# hellobusbridge_button.net
KiCad netlist of a schematic drawn in EAGLE
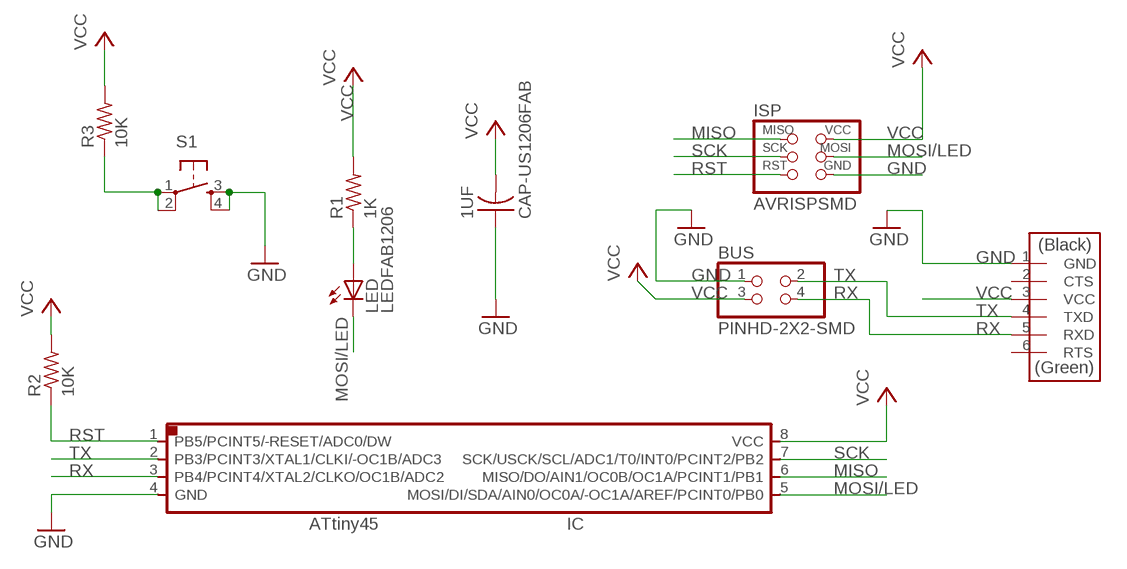
[diagram p0: schematic, sheet 1]

(export (version "E")
  (design (tool "Eeschema 10.0.6"))
  (components
    (comp (ref "1UF")
      (value "CAP-US1206FAB")
      (footprint "eagle-import:C1206FAB")
      (libsource (lib "eagle-import") (part "CAP-US1206FAB"))
    )
    (comp (ref "BUS")
      (value "PINHD-2X2-SMD")
      (footprint "eagle-import:2X02SMD")
      (libsource (lib "eagle-import") (part "PINHD-2X2-SMD"))
    )
    (comp (ref "IC")
      (value "IC")
      (footprint "eagle-import:SOIC8")
      (libsource (lib "eagle-import") (part "ATTINY45SI"))
    )
    (comp (ref "ISP")
      (value "AVRISPSMD")
      (footprint "eagle-import:2X03SMD")
      (libsource (lib "eagle-import") (part "AVRISPSMD"))
    )
    (comp (ref "LED")
      (value "LEDFAB1206")
      (footprint "eagle-import:LED1206FAB")
      (libsource (lib "eagle-import") (part "LEDFAB1206"))
    )
    (comp (ref "R1")
      (value "1K")
      (footprint "eagle-import:R1206FAB")
      (libsource (lib "eagle-import") (part "RES-US1206FAB"))
    )
    (comp (ref "R2")
      (value "10K")
      (footprint "eagle-import:R1206FAB")
      (libsource (lib "eagle-import") (part "RES-US1206FAB"))
    )
    (comp (ref "R3")
      (value "10K")
      (footprint "eagle-import:R1206FAB")
      (libsource (lib "eagle-import") (part "RES-US1206FAB"))
    )
    (comp (ref "S1")
      (value "6MM_SWITCH6MM_SWITCH")
      (footprint "eagle-import:6MM_SWITCH")
      (libsource (lib "eagle-import") (part "6MM_SWITCH6MM_SWITCH"))
    )
    (comp (ref "U$5")
      (value "FTDI-SMD-HEADER")
      (footprint "eagle-import:1X06SMD")
      (libsource (lib "eagle-import") (part "FTDI-SMD-HEADER"))
    )
  )
  (nets
    (net (code "1") (name "/MISO") (class "Default")
      (node (ref "IC") (pin "6") (pinfunction "MISO/DO/AIN1/OC0B/OC1A/PCINT1/PB1_6") (pintype "bidirectional"))
      (node (ref "ISP") (pin "1") (pinfunction "MISO_1") (pintype "passive"))
      (node (ref "R3") (pin "1") (pinfunction "1_1") (pintype "passive"))
      (node (ref "S1") (pin "1") (pinfunction "P_1") (pintype "passive"))
      (node (ref "S1") (pin "2") (pinfunction "P1_2") (pintype "passive"))
    )
    (net (code "2") (name "/MOSI{slash}LED") (class "Default")
      (node (ref "IC") (pin "5") (pinfunction "MOSI/DI/SDA/AIN0/OC0A/-OC1A/AREF/PCINT0/PB0_5") (pintype "bidirectional"))
      (node (ref "ISP") (pin "4") (pinfunction "MOSI_4") (pintype "passive"))
      (node (ref "LED") (pin "2") (pinfunction "C_2") (pintype "passive"))
    )
    (net (code "3") (name "/RST") (class "Default")
      (node (ref "IC") (pin "1") (pinfunction "PB5/PCINT5/-RESET/ADC0/DW_1") (pintype "bidirectional"))
      (node (ref "ISP") (pin "5") (pinfunction "RST_5") (pintype "passive"))
      (node (ref "R2") (pin "1") (pinfunction "1_1") (pintype "passive"))
    )
    (net (code "4") (name "/RX") (class "Default")
      (node (ref "BUS") (pin "4") (pinfunction "4_4") (pintype "passive"))
      (node (ref "IC") (pin "3") (pinfunction "PB4/PCINT4/XTAL2/CLKO/OC1B/ADC2_3") (pintype "bidirectional"))
      (node (ref "U$5") (pin "5") (pinfunction "RXD_5") (pintype "bidirectional"))
    )
    (net (code "5") (name "/SCK") (class "Default")
      (node (ref "IC") (pin "7") (pinfunction "SCK/USCK/SCL/ADC1/T0/INT0/PCINT2/PB2_7") (pintype "bidirectional"))
      (node (ref "ISP") (pin "3") (pinfunction "SCK_3") (pintype "passive"))
    )
    (net (code "6") (name "/TX") (class "Default")
      (node (ref "BUS") (pin "2") (pinfunction "2_2") (pintype "passive"))
      (node (ref "IC") (pin "2") (pinfunction "PB3/PCINT3/XTAL1/CLKI/-OC1B/ADC3_2") (pintype "bidirectional"))
      (node (ref "U$5") (pin "4") (pinfunction "TXD_4") (pintype "bidirectional"))
    )
    (net (code "7") (name "GND") (class "Default")
      (node (ref "1UF") (pin "1") (pinfunction "1_1") (pintype "passive"))
      (node (ref "BUS") (pin "1") (pinfunction "1_1") (pintype "passive"))
      (node (ref "IC") (pin "4") (pinfunction "GND_4") (pintype "bidirectional"))
      (node (ref "ISP") (pin "6") (pinfunction "GND_6") (pintype "passive"))
      (node (ref "S1") (pin "3") (pinfunction "S_3") (pintype "passive"))
      (node (ref "S1") (pin "4") (pinfunction "S1_4") (pintype "passive"))
      (node (ref "U$5") (pin "1") (pinfunction "GND_1") (pintype "bidirectional"))
    )
    (net (code "8") (name "Net-(LED-A)") (class "Default")
      (node (ref "LED") (pin "1") (pinfunction "A_1") (pintype "passive"))
      (node (ref "R1") (pin "1") (pinfunction "1_1") (pintype "passive"))
    )
    (net (code "9") (name "VCC") (class "Default")
      (node (ref "1UF") (pin "2") (pinfunction "2_2") (pintype "passive"))
      (node (ref "BUS") (pin "3") (pinfunction "3_3") (pintype "passive"))
      (node (ref "IC") (pin "8") (pinfunction "VCC_8") (pintype "bidirectional"))
      (node (ref "ISP") (pin "2") (pinfunction "VCC_2") (pintype "passive"))
      (node (ref "R1") (pin "2") (pinfunction "2_2") (pintype "passive"))
      (node (ref "R2") (pin "2") (pinfunction "2_2") (pintype "passive"))
      (node (ref "R3") (pin "2") (pinfunction "2_2") (pintype "passive"))
      (node (ref "U$5") (pin "3") (pinfunction "VCC_3") (pintype "bidirectional"))
    )
    (net (code "10") (name "unconnected-(U$5-CTS-Pad2)") (class "Default")
      (node (ref "U$5") (pin "2") (pinfunction "CTS_2") (pintype "bidirectional"))
    )
    (net (code "11") (name "unconnected-(U$5-RTS-Pad6)") (class "Default")
      (node (ref "U$5") (pin "6") (pinfunction "RTS_6") (pintype "bidirectional"))
    )
  )
)
